# 2MosfetV2.net
KiCad netlist of a schematic drawn in EAGLE
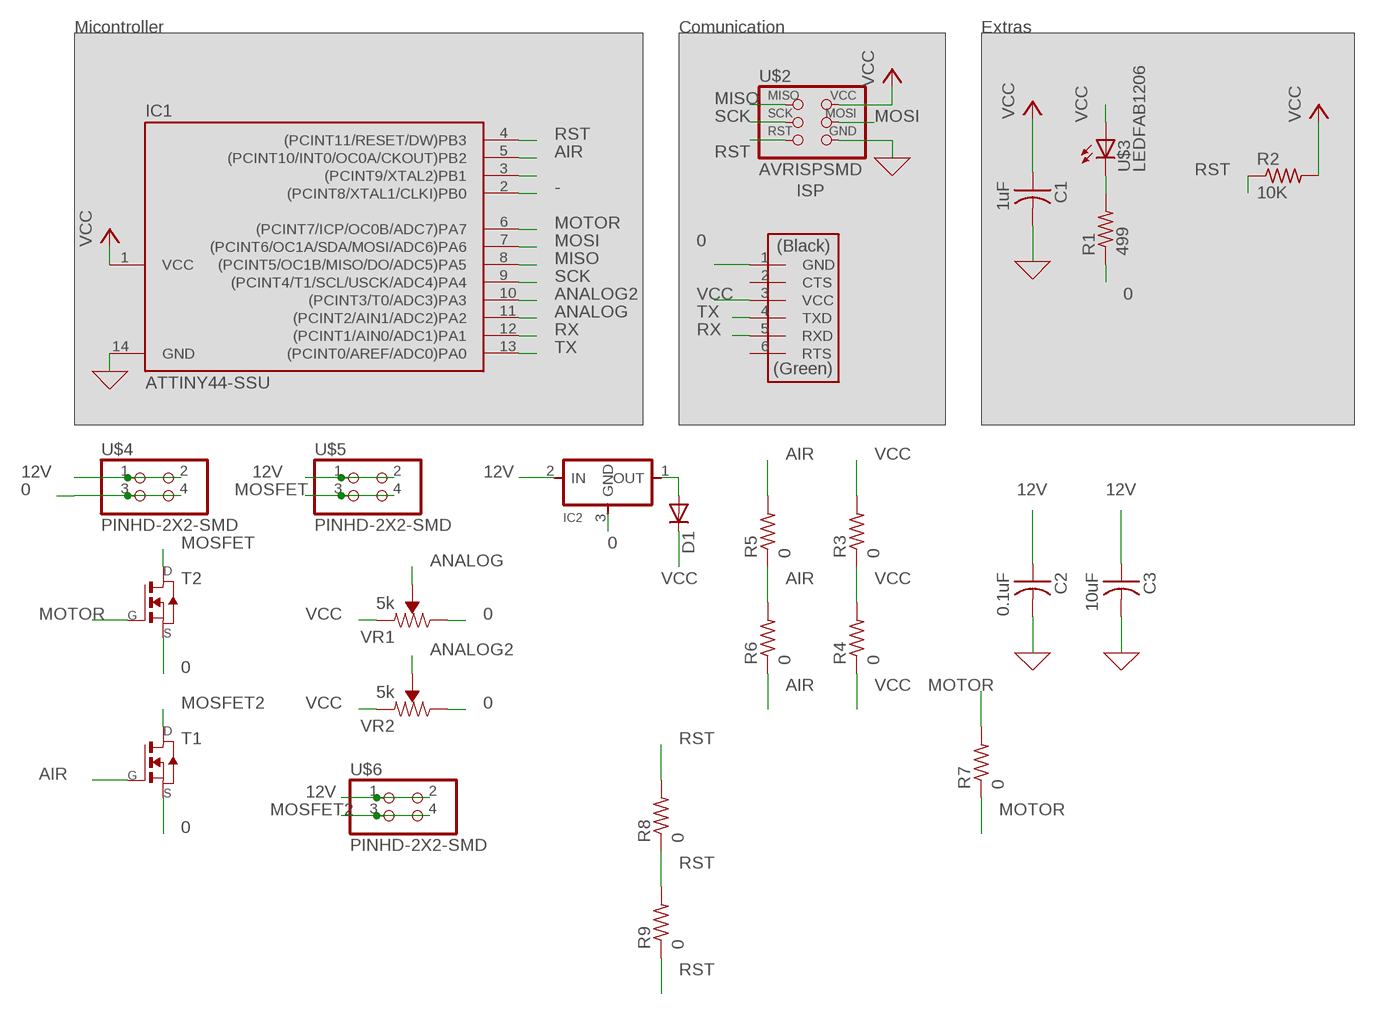
[diagram p0: schematic, sheet 1]

(export (version "E")
  (design (tool "Eeschema 10.0.6"))
  (components
    (comp (ref "C1")
      (value "1uF")
      (footprint "eagle-import:C1206FAB")
      (libsource (lib "eagle-import") (part "CAP-US1206FAB"))
    )
    (comp (ref "C2")
      (value "0.1uF")
      (footprint "eagle-import:C1206FAB")
      (libsource (lib "eagle-import") (part "CAP-US1206FAB"))
    )
    (comp (ref "C3")
      (value "10uF")
      (footprint "eagle-import:C1206FAB")
      (libsource (lib "eagle-import") (part "CAP-US1206FAB"))
    )
    (comp (ref "D1")
      (value "DIODESOD123")
      (footprint "eagle-import:SOD123")
      (libsource (lib "eagle-import") (part "DIODESOD123"))
    )
    (comp (ref "IC1")
      (value "ATTINY44-SSU")
      (footprint "eagle-import:SOIC14")
      (libsource (lib "eagle-import") (part "ATTINY44-SSU"))
    )
    (comp (ref "IC2")
      (value "REGULATORSOT23")
      (footprint "eagle-import:SOT23")
      (libsource (lib "eagle-import") (part "REGULATORSOT23"))
    )
    (comp (ref "R1")
      (value "499")
      (footprint "eagle-import:R1206FAB")
      (libsource (lib "eagle-import") (part "RES-US1206FAB"))
    )
    (comp (ref "R2")
      (value "10K")
      (footprint "eagle-import:R1206FAB")
      (libsource (lib "eagle-import") (part "RES-US1206FAB"))
    )
    (comp (ref "R3")
      (value "0")
      (footprint "eagle-import:R1206FAB")
      (libsource (lib "eagle-import") (part "RES-US1206FAB"))
    )
    (comp (ref "R4")
      (value "0")
      (footprint "eagle-import:R1206FAB")
      (libsource (lib "eagle-import") (part "RES-US1206FAB"))
    )
    (comp (ref "R5")
      (value "0")
      (footprint "eagle-import:R1206FAB")
      (libsource (lib "eagle-import") (part "RES-US1206FAB"))
    )
    (comp (ref "R6")
      (value "0")
      (footprint "eagle-import:R1206FAB")
      (libsource (lib "eagle-import") (part "RES-US1206FAB"))
    )
    (comp (ref "R7")
      (value "0")
      (footprint "eagle-import:R1206FAB")
      (libsource (lib "eagle-import") (part "RES-US1206FAB"))
    )
    (comp (ref "R8")
      (value "0")
      (footprint "eagle-import:R1206FAB")
      (libsource (lib "eagle-import") (part "RES-US1206FAB"))
    )
    (comp (ref "R9")
      (value "0")
      (footprint "eagle-import:R1206FAB")
      (libsource (lib "eagle-import") (part "RES-US1206FAB"))
    )
    (comp (ref "T1")
      (value "NMOSFETTO252")
      (footprint "eagle-import:TO252")
      (libsource (lib "eagle-import") (part "NMOSFETTO252"))
    )
    (comp (ref "T2")
      (value "NMOSFETTO252")
      (footprint "eagle-import:TO252")
      (libsource (lib "eagle-import") (part "NMOSFETTO252"))
    )
    (comp (ref "U$1")
      (value "FTDI-SMD-HEADER")
      (footprint "eagle-import:1X06SMD")
      (libsource (lib "eagle-import") (part "FTDI-SMD-HEADER"))
    )
    (comp (ref "U$2")
      (value "AVRISPSMD")
      (footprint "eagle-import:2X03SMD")
      (libsource (lib "eagle-import") (part "AVRISPSMD"))
    )
    (comp (ref "U$3")
      (value "LEDFAB1206")
      (footprint "eagle-import:LED1206FAB")
      (libsource (lib "eagle-import") (part "LEDFAB1206"))
    )
    (comp (ref "U$4")
      (value "PINHD-2X2-SMD")
      (footprint "eagle-import:2X02SMD")
      (libsource (lib "eagle-import") (part "PINHD-2X2-SMD"))
    )
    (comp (ref "U$5")
      (value "PINHD-2X2-SMD")
      (footprint "eagle-import:2X02SMD")
      (libsource (lib "eagle-import") (part "PINHD-2X2-SMD"))
    )
    (comp (ref "U$6")
      (value "PINHD-2X2-SMD")
      (footprint "eagle-import:2X02SMD")
      (libsource (lib "eagle-import") (part "PINHD-2X2-SMD"))
    )
    (comp (ref "VR1")
      (value "5k")
      (footprint "eagle-import:TRIMPOT-SMD-5MM")
      (libsource (lib "eagle-import") (part "TRIMPOT-SMD-5MM-CLOSED-1/4W-20%"))
    )
    (comp (ref "VR2")
      (value "5k")
      (footprint "eagle-import:TRIMPOT-SMD-5MM")
      (libsource (lib "eagle-import") (part "TRIMPOT-SMD-5MM-CLOSED-1/4W-20%"))
    )
  )
  (nets
    (net (code "1") (name "/-") (class "Default")
      (node (ref "IC1") (pin "2") (pinfunction "(PCINT8/XTAL1/CLKI)PB0_2") (pintype "bidirectional"))
    )
    (net (code "2") (name "/12V") (class "Default")
      (node (ref "C2") (pin "1") (pinfunction "1_1") (pintype "passive"))
      (node (ref "C3") (pin "1") (pinfunction "1_1") (pintype "passive"))
      (node (ref "IC2") (pin "2") (pinfunction "IN_2") (pintype "bidirectional"))
      (node (ref "U$4") (pin "1") (pinfunction "1_1") (pintype "passive"))
      (node (ref "U$4") (pin "2") (pinfunction "2_2") (pintype "passive"))
      (node (ref "U$5") (pin "1") (pinfunction "1_1") (pintype "passive"))
      (node (ref "U$5") (pin "2") (pinfunction "2_2") (pintype "passive"))
      (node (ref "U$6") (pin "1") (pinfunction "1_1") (pintype "passive"))
      (node (ref "U$6") (pin "2") (pinfunction "2_2") (pintype "passive"))
    )
    (net (code "3") (name "/AIR") (class "Default")
      (node (ref "IC1") (pin "5") (pinfunction "(PCINT10/INT0/OC0A/CKOUT)PB2_5") (pintype "bidirectional"))
      (node (ref "R5") (pin "1") (pinfunction "1_1") (pintype "passive"))
      (node (ref "R5") (pin "2") (pinfunction "2_2") (pintype "passive"))
      (node (ref "R6") (pin "1") (pinfunction "1_1") (pintype "passive"))
      (node (ref "R6") (pin "2") (pinfunction "2_2") (pintype "passive"))
      (node (ref "T1") (pin "1") (pinfunction "G_1") (pintype "passive"))
    )
    (net (code "4") (name "/ANALOG") (class "Default")
      (node (ref "IC1") (pin "11") (pinfunction "(PCINT2/AIN1/ADC2)PA2_11") (pintype "bidirectional"))
      (node (ref "VR1") (pin "B") (pinfunction "WIPER_B") (pintype "passive"))
    )
    (net (code "5") (name "/ANALOG2") (class "Default")
      (node (ref "IC1") (pin "10") (pinfunction "(PCINT3/T0/ADC3)PA3_10") (pintype "bidirectional"))
      (node (ref "VR2") (pin "B") (pinfunction "WIPER_B") (pintype "passive"))
    )
    (net (code "6") (name "/MISO") (class "Default")
      (node (ref "IC1") (pin "8") (pinfunction "(PCINT5/OC1B/MISO/DO/ADC5)PA5_8") (pintype "bidirectional"))
      (node (ref "U$2") (pin "1") (pinfunction "MISO_1") (pintype "passive"))
    )
    (net (code "7") (name "/MOSFET") (class "Default")
      (node (ref "T2") (pin "3") (pinfunction "D_3") (pintype "passive"))
      (node (ref "U$5") (pin "3") (pinfunction "3_3") (pintype "passive"))
      (node (ref "U$5") (pin "4") (pinfunction "4_4") (pintype "passive"))
    )
    (net (code "8") (name "/MOSFET2") (class "Default")
      (node (ref "T1") (pin "3") (pinfunction "D_3") (pintype "passive"))
      (node (ref "U$6") (pin "3") (pinfunction "3_3") (pintype "passive"))
      (node (ref "U$6") (pin "4") (pinfunction "4_4") (pintype "passive"))
    )
    (net (code "9") (name "/MOSI") (class "Default")
      (node (ref "IC1") (pin "7") (pinfunction "(PCINT6/OC1A/SDA/MOSI/ADC6)PA6_7") (pintype "bidirectional"))
      (node (ref "U$2") (pin "4") (pinfunction "MOSI_4") (pintype "passive"))
    )
    (net (code "10") (name "/MOTOR") (class "Default")
      (node (ref "IC1") (pin "6") (pinfunction "(PCINT7/ICP/OC0B/ADC7)PA7_6") (pintype "bidirectional"))
      (node (ref "R7") (pin "1") (pinfunction "1_1") (pintype "passive"))
      (node (ref "R7") (pin "2") (pinfunction "2_2") (pintype "passive"))
      (node (ref "T2") (pin "1") (pinfunction "G_1") (pintype "passive"))
    )
    (net (code "11") (name "/RST") (class "Default")
      (node (ref "IC1") (pin "4") (pinfunction "(PCINT11/RESET/DW)PB3_4") (pintype "bidirectional"))
      (node (ref "R2") (pin "1") (pinfunction "1_1") (pintype "passive"))
      (node (ref "R8") (pin "1") (pinfunction "1_1") (pintype "passive"))
      (node (ref "R8") (pin "2") (pinfunction "2_2") (pintype "passive"))
      (node (ref "R9") (pin "1") (pinfunction "1_1") (pintype "passive"))
      (node (ref "R9") (pin "2") (pinfunction "2_2") (pintype "passive"))
      (node (ref "U$2") (pin "5") (pinfunction "RST_5") (pintype "passive"))
    )
    (net (code "12") (name "/RX") (class "Default")
      (node (ref "IC1") (pin "12") (pinfunction "(PCINT1/AIN0/ADC1)PA1_12") (pintype "bidirectional"))
      (node (ref "U$1") (pin "5") (pinfunction "RXD_5") (pintype "bidirectional"))
    )
    (net (code "13") (name "/SCK") (class "Default")
      (node (ref "IC1") (pin "9") (pinfunction "(PCINT4/T1/SCL/USCK/ADC4)PA4_9") (pintype "bidirectional"))
      (node (ref "U$2") (pin "3") (pinfunction "SCK_3") (pintype "passive"))
    )
    (net (code "14") (name "/TX") (class "Default")
      (node (ref "IC1") (pin "13") (pinfunction "(PCINT0/AREF/ADC0)PA0_13") (pintype "bidirectional"))
      (node (ref "U$1") (pin "4") (pinfunction "TXD_4") (pintype "bidirectional"))
    )
    (net (code "15") (name "GND") (class "Default")
      (node (ref "C1") (pin "2") (pinfunction "2_2") (pintype "passive"))
      (node (ref "C2") (pin "2") (pinfunction "2_2") (pintype "passive"))
      (node (ref "C3") (pin "2") (pinfunction "2_2") (pintype "passive"))
      (node (ref "IC1") (pin "14") (pinfunction "GND_14") (pintype "power_in"))
      (node (ref "IC2") (pin "3") (pinfunction "GND_3") (pintype "bidirectional"))
      (node (ref "R1") (pin "1") (pinfunction "1_1") (pintype "passive"))
      (node (ref "T1") (pin "2") (pinfunction "S_2") (pintype "passive"))
      (node (ref "T2") (pin "2") (pinfunction "S_2") (pintype "passive"))
      (node (ref "U$1") (pin "1") (pinfunction "GND_1") (pintype "bidirectional"))
      (node (ref "U$2") (pin "6") (pinfunction "GND_6") (pintype "passive"))
      (node (ref "U$4") (pin "3") (pinfunction "3_3") (pintype "passive"))
      (node (ref "U$4") (pin "4") (pinfunction "4_4") (pintype "passive"))
      (node (ref "VR1") (pin "C") (pinfunction "CW_C") (pintype "passive"))
      (node (ref "VR2") (pin "C") (pinfunction "CW_C") (pintype "passive"))
    )
    (net (code "16") (name "Net-(D1-A)") (class "Default")
      (node (ref "D1") (pin "ANODE") (pinfunction "A_ANODE") (pintype "passive"))
      (node (ref "IC2") (pin "1") (pinfunction "OUT_1") (pintype "bidirectional"))
    )
    (net (code "17") (name "Net-(U$3-C)") (class "Default")
      (node (ref "R1") (pin "2") (pinfunction "2_2") (pintype "passive"))
      (node (ref "U$3") (pin "2") (pinfunction "C_2") (pintype "passive"))
    )
    (net (code "18") (name "VCC") (class "Default")
      (node (ref "C1") (pin "1") (pinfunction "1_1") (pintype "passive"))
      (node (ref "D1") (pin "CATHODE") (pinfunction "C_CATHODE") (pintype "passive"))
      (node (ref "IC1") (pin "1") (pinfunction "VCC_1") (pintype "power_in"))
      (node (ref "R2") (pin "2") (pinfunction "2_2") (pintype "passive"))
      (node (ref "R3") (pin "1") (pinfunction "1_1") (pintype "passive"))
      (node (ref "R3") (pin "2") (pinfunction "2_2") (pintype "passive"))
      (node (ref "R4") (pin "1") (pinfunction "1_1") (pintype "passive"))
      (node (ref "R4") (pin "2") (pinfunction "2_2") (pintype "passive"))
      (node (ref "U$1") (pin "3") (pinfunction "VCC_3") (pintype "bidirectional"))
      (node (ref "U$2") (pin "2") (pinfunction "VCC_2") (pintype "passive"))
      (node (ref "U$3") (pin "1") (pinfunction "A_1") (pintype "passive"))
      (node (ref "VR1") (pin "A") (pinfunction "CCW_A") (pintype "passive"))
      (node (ref "VR2") (pin "A") (pinfunction "CCW_A") (pintype "passive"))
    )
    (net (code "19") (name "unconnected-(IC1-(PCINT9{slash}XTAL2)PB1-Pad3)") (class "Default")
      (node (ref "IC1") (pin "3") (pinfunction "(PCINT9/XTAL2)PB1_3") (pintype "bidirectional"))
    )
    (net (code "20") (name "unconnected-(U$1-CTS-Pad2)") (class "Default")
      (node (ref "U$1") (pin "2") (pinfunction "CTS_2") (pintype "bidirectional"))
    )
    (net (code "21") (name "unconnected-(U$1-RTS-Pad6)") (class "Default")
      (node (ref "U$1") (pin "6") (pinfunction "RTS_6") (pintype "bidirectional"))
    )
  )
)
